# reefpi_pico_toplevel.net
KiCad netlist of a schematic drawn in Altium Designer
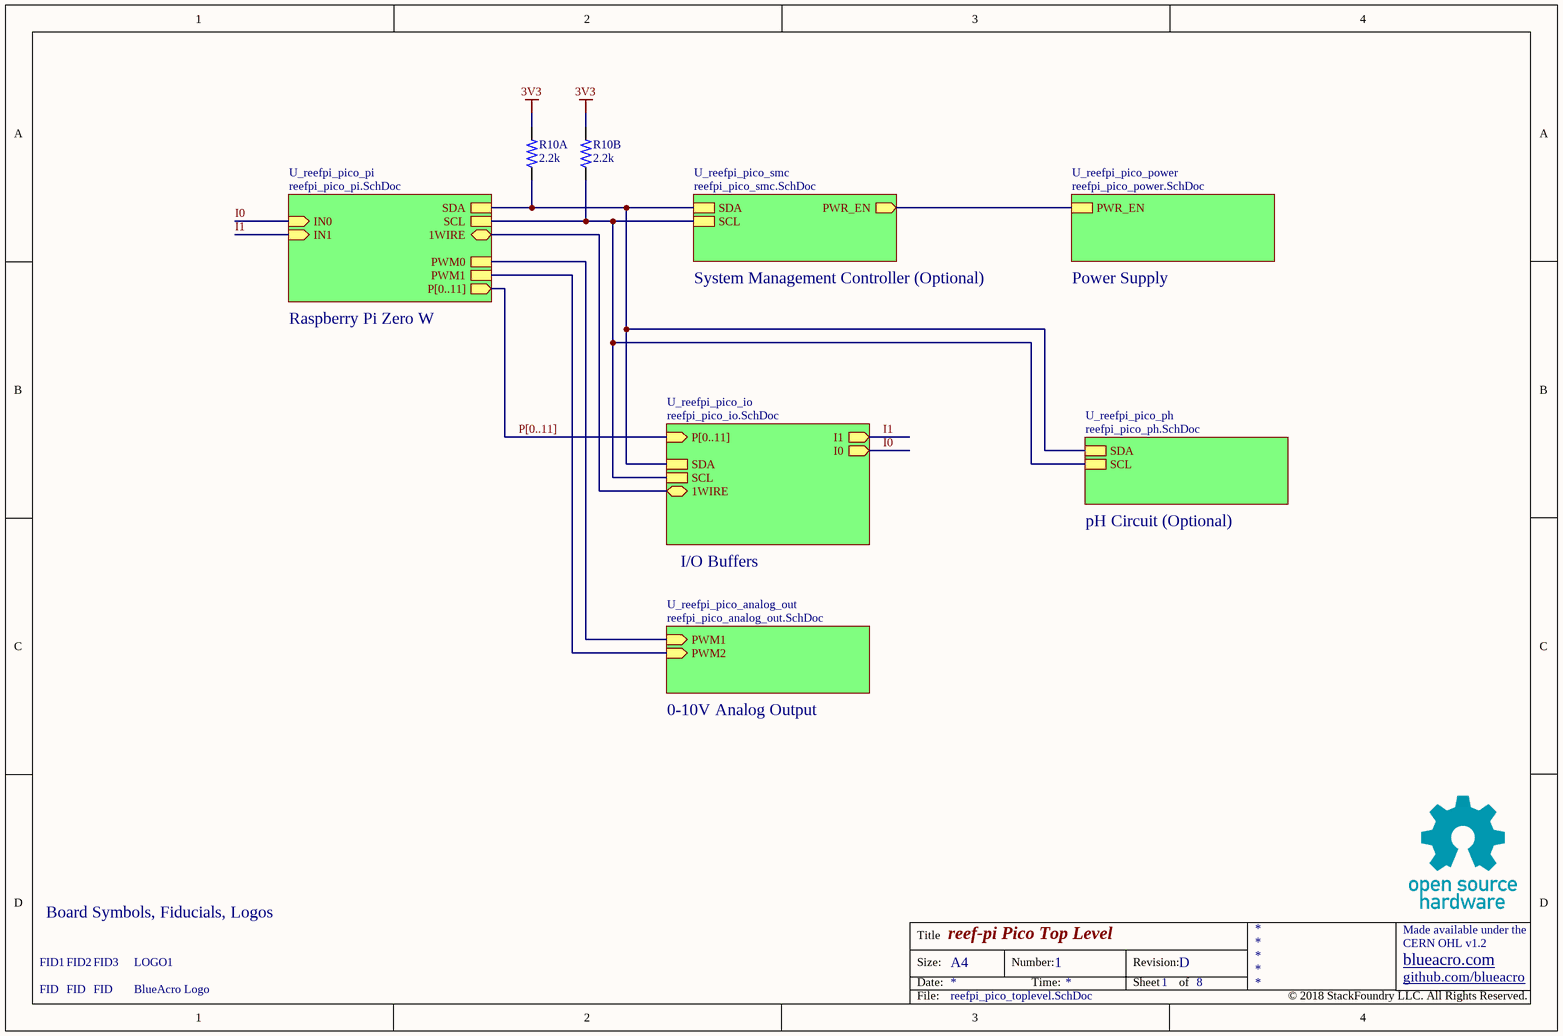
[diagram p0: reefpi_pico_toplevel.SchDoc]

(export (version "E")
  (design (tool "Eeschema 10.0.6"))
  (components
    (comp (ref "FID1") (value "FID") (footprint "FIDUCIAL_1MM") (libsource (lib "testpoints") (part "FID")))
    (comp (ref "FID2") (value "FID") (footprint "FIDUCIAL_1MM") (libsource (lib "testpoints") (part "FID")))
    (comp (ref "FID3") (value "FID") (footprint "FIDUCIAL_1MM") (libsource (lib "testpoints") (part "FID")))
    (comp (ref "LOGO1")
      (value "BlueAcro Logo")
      (footprint "BLUEACRO_LOGO_500MIL")
      (libsource (lib "logos") (part "BlueAcro Logo"))
    )
    (comp (ref "R10") (value "2.2k") (footprint "R0603x4") (libsource (lib "rcl") (part "R-US-4ch")))
  )
  (nets
    (net (code "20") (name "/SCL") (class "Default")
      (node (ref "R10") (pin "3") (pinfunction "3_3") (pintype "passive"))
    )
    (net (code "21") (name "/SDA") (class "Default")
      (node (ref "R10") (pin "1") (pinfunction "1_1") (pintype "passive"))
    )
    (net (code "22") (name "3V3") (class "Default")
      (node (ref "R10") (pin "2") (pinfunction "2_2") (pintype "passive"))
      (node (ref "R10") (pin "4") (pinfunction "4_4") (pintype "passive"))
    )
  )
)
